# SENSOR_SCH_HDMI.net
KiCad netlist of a schematic drawn in EasyEDA
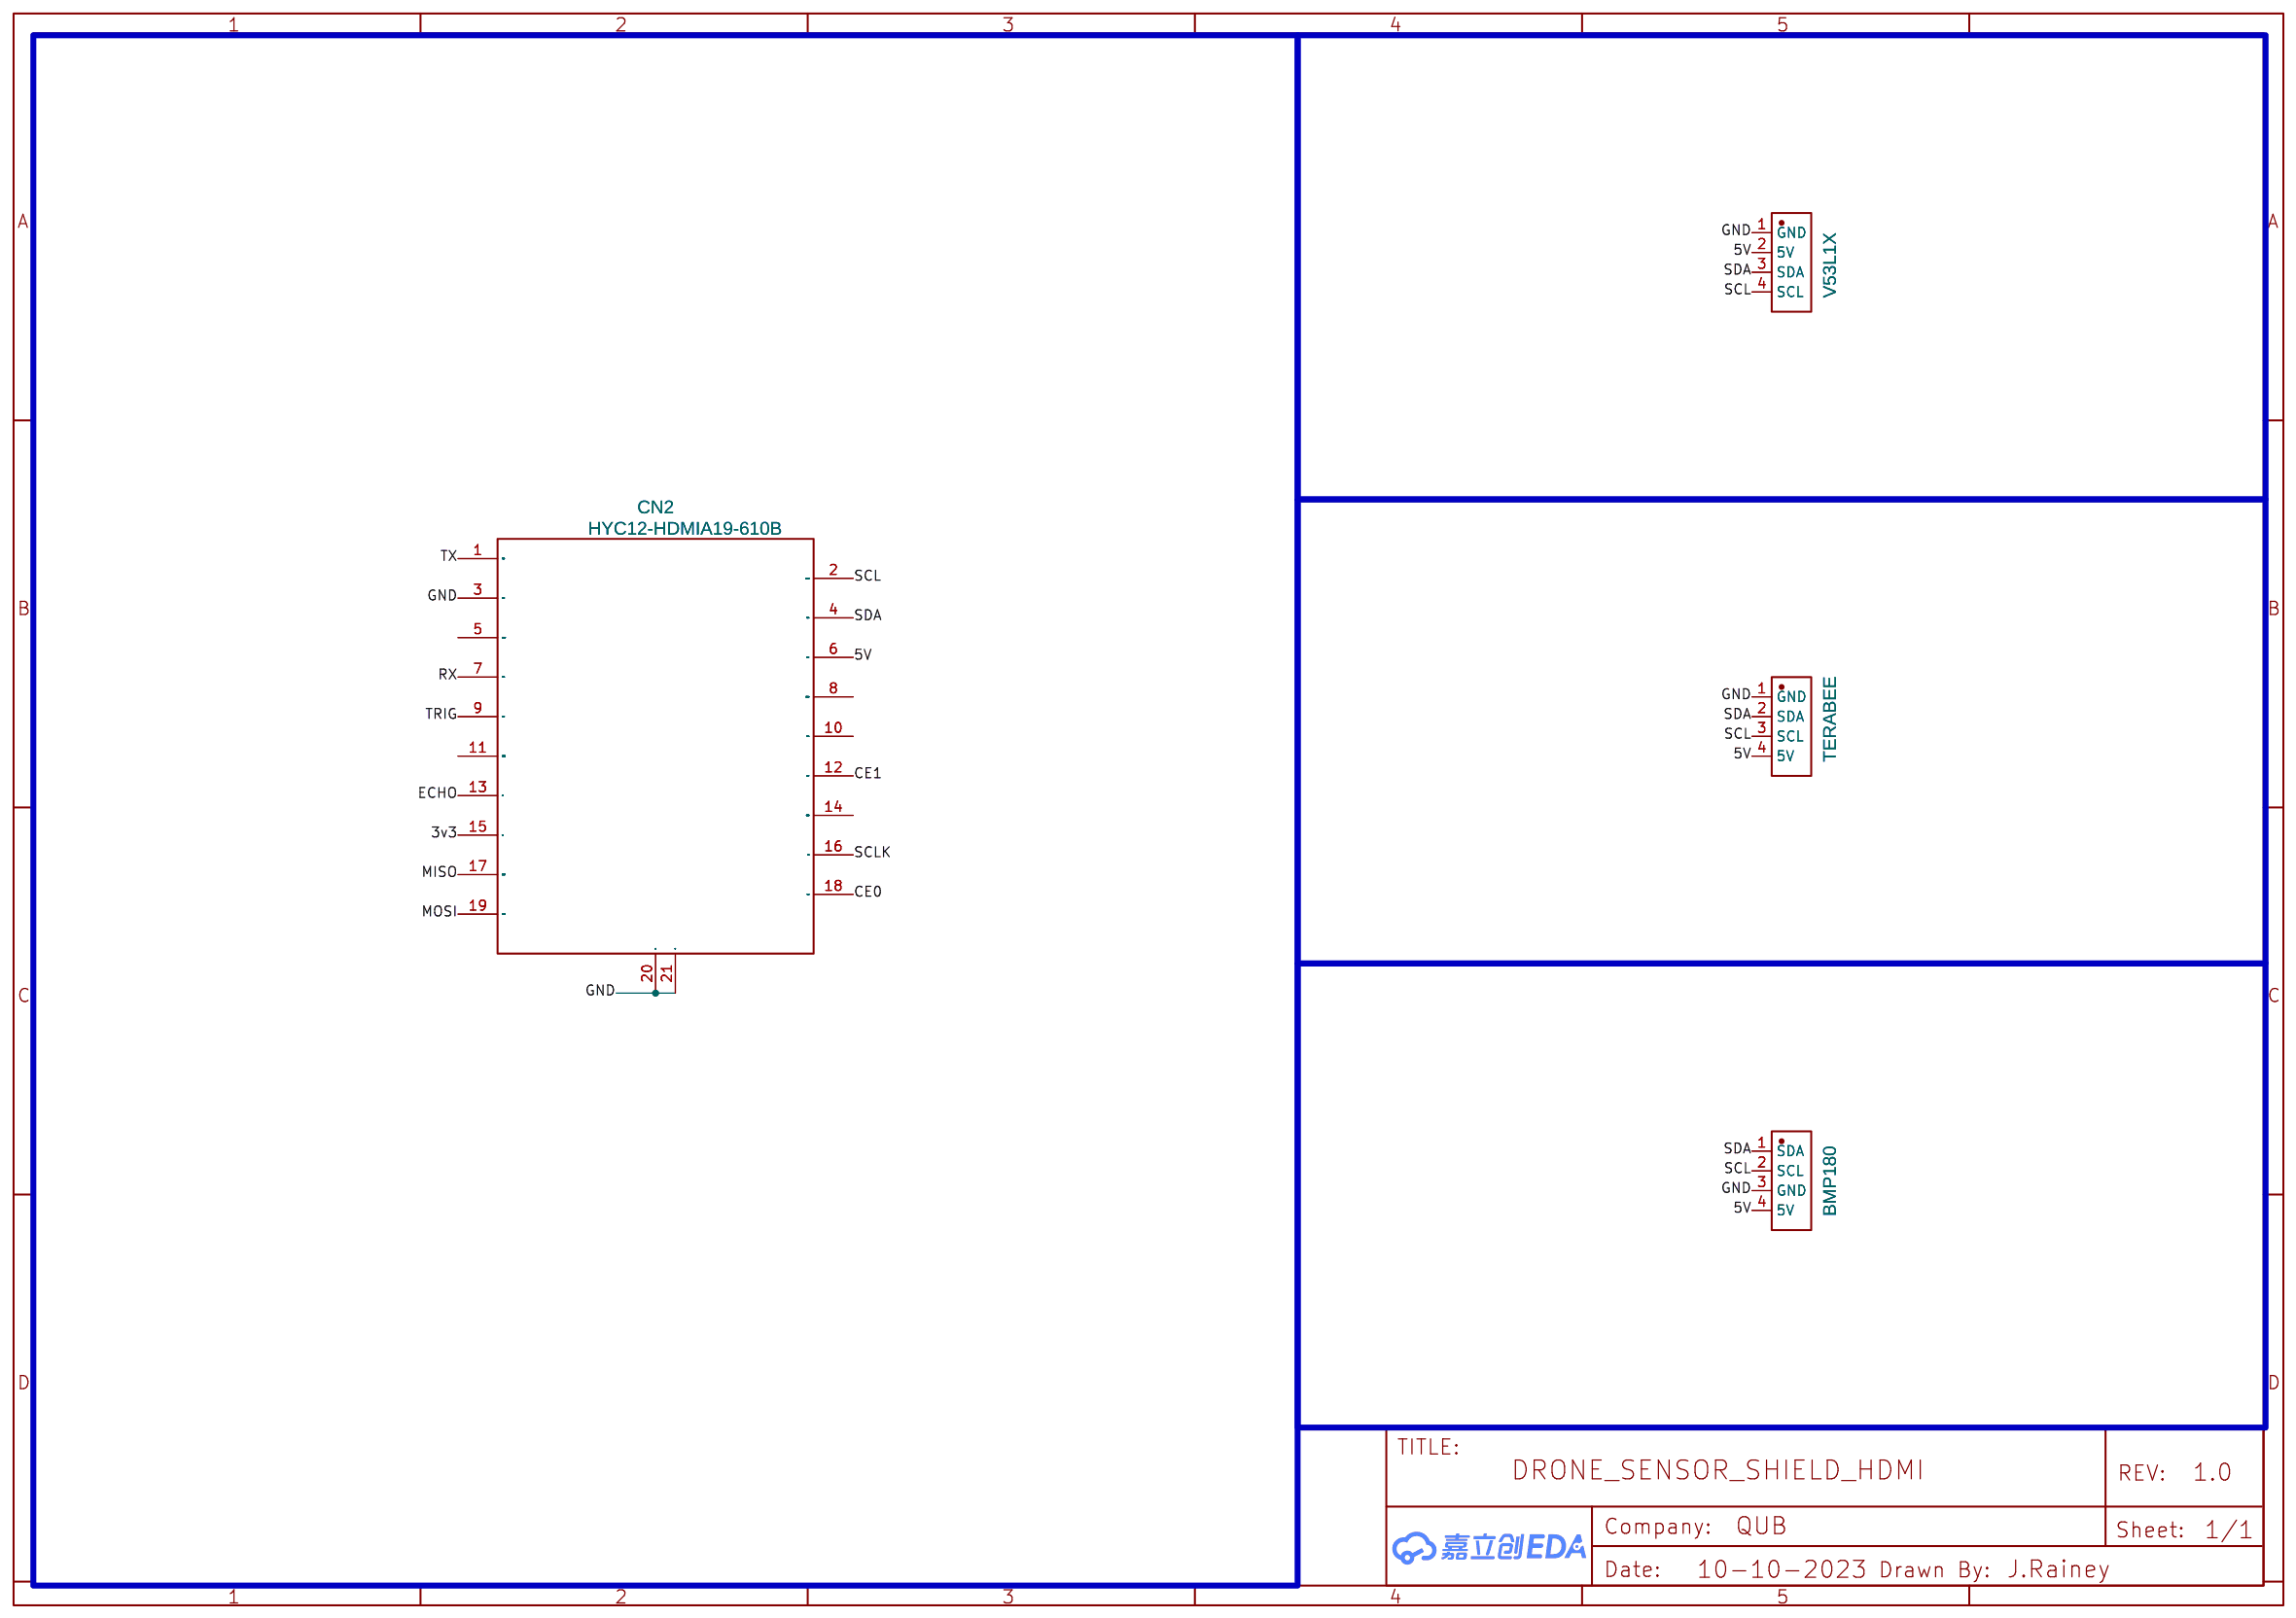
[diagram p0: schematic sheet]

(export (version "E")
  (design (tool "Eeschema 10.0.6"))
  (components
    (comp (ref "BMP180")
      (value "PZ254V-11-04P")
      (fields (field (name "BOM_Supplier Part") "C492403"))
      (libsource (lib "") (part "PZ254V-11-04P_2"))
    )
    (comp (ref "CN2")
      (value "HYC12-HDMIA19-610B")
      (fields (field (name "BOM_Supplier Part") "C711354"))
      (libsource (lib "") (part "HYC12-HDMIA19-610B"))
    )
    (comp (ref "TERABEE")
      (value "PZ254V-11-04P")
      (fields (field (name "BOM_Supplier Part") "C492403"))
      (libsource (lib "") (part "PZ254V-11-04P"))
    )
    (comp (ref "V53L1X")
      (value "PZ254V-11-04P")
      (fields (field (name "BOM_Supplier Part") "C492403"))
      (libsource (lib "") (part "PZ254V-11-04P_1"))
    )
  )
  (nets
    (net (code "1") (name "/3v3") (class "Default")
      (node (ref "CN2") (pin "15") (pinfunction "SCL_15") (pintype "unspecified"))
    )
    (net (code "2") (name "/5V") (class "Default")
      (node (ref "BMP180") (pin "4") (pinfunction "5V_4") (pintype "unspecified"))
      (node (ref "CN2") (pin "6") (pinfunction "TMDS_Data_1-_6") (pintype "unspecified"))
      (node (ref "TERABEE") (pin "4") (pinfunction "5V_4") (pintype "unspecified"))
      (node (ref "V53L1X") (pin "2") (pinfunction "5V_2") (pintype "unspecified"))
    )
    (net (code "3") (name "/CE0") (class "Default")
      (node (ref "CN2") (pin "18") (pinfunction "+5V_Power_18") (pintype "unspecified"))
    )
    (net (code "4") (name "/CE1") (class "Default")
      (node (ref "CN2") (pin "12") (pinfunction "TMDS_Clock-_12") (pintype "unspecified"))
    )
    (net (code "5") (name "/ECHO") (class "Default")
      (node (ref "CN2") (pin "13") (pinfunction "CEC_13") (pintype "unspecified"))
    )
    (net (code "6") (name "/GND") (class "Default")
      (node (ref "BMP180") (pin "3") (pinfunction "GND_3") (pintype "unspecified"))
      (node (ref "CN2") (pin "20") (pinfunction "EH_20") (pintype "unspecified"))
      (node (ref "CN2") (pin "21") (pinfunction "EH_21") (pintype "unspecified"))
      (node (ref "CN2") (pin "3") (pinfunction "TMDS_Data_2-_3") (pintype "unspecified"))
      (node (ref "TERABEE") (pin "1") (pinfunction "GND_1") (pintype "unspecified"))
      (node (ref "V53L1X") (pin "1") (pinfunction "GND_1") (pintype "unspecified"))
    )
    (net (code "7") (name "/MISO") (class "Default")
      (node (ref "CN2") (pin "17") (pinfunction "DDC/CEC_Ground_17") (pintype "unspecified"))
    )
    (net (code "8") (name "/MOSI") (class "Default")
      (node (ref "CN2") (pin "19") (pinfunction "Hot_Plug_Detect_19") (pintype "unspecified"))
    )
    (net (code "9") (name "/RX") (class "Default")
      (node (ref "CN2") (pin "7") (pinfunction "TMDS_Data_0+_7") (pintype "unspecified"))
    )
    (net (code "10") (name "/SCL") (class "Default")
      (node (ref "BMP180") (pin "2") (pinfunction "SCL_2") (pintype "unspecified"))
      (node (ref "CN2") (pin "2") (pinfunction "TMDS_Data_2_Shield_2") (pintype "unspecified"))
      (node (ref "TERABEE") (pin "3") (pinfunction "SCL_3") (pintype "unspecified"))
      (node (ref "V53L1X") (pin "4") (pinfunction "SCL_4") (pintype "unspecified"))
    )
    (net (code "11") (name "/SCLK") (class "Default")
      (node (ref "CN2") (pin "16") (pinfunction "SDA_16") (pintype "unspecified"))
    )
    (net (code "12") (name "/SDA") (class "Default")
      (node (ref "BMP180") (pin "1") (pinfunction "SDA_1") (pintype "unspecified"))
      (node (ref "CN2") (pin "4") (pinfunction "TMDS_Data_1+_4") (pintype "unspecified"))
      (node (ref "TERABEE") (pin "2") (pinfunction "SDA_2") (pintype "unspecified"))
      (node (ref "V53L1X") (pin "3") (pinfunction "SDA_3") (pintype "unspecified"))
    )
    (net (code "13") (name "/TRIG") (class "Default")
      (node (ref "CN2") (pin "9") (pinfunction "TMDS_Data_0-_9") (pintype "unspecified"))
    )
    (net (code "14") (name "/TX") (class "Default")
      (node (ref "CN2") (pin "1") (pinfunction "TMDS_Data_2+_1") (pintype "unspecified"))
    )
    (net (code "15") (name "unconnected-(CN2-Reserved_(N.C.)-Pad14)") (class "Default")
      (node (ref "CN2") (pin "14") (pinfunction "Reserved_(N.C.)_14") (pintype "unspecified"))
    )
    (net (code "16") (name "unconnected-(CN2-TMDS_Clock+-Pad10)") (class "Default")
      (node (ref "CN2") (pin "10") (pinfunction "TMDS_Clock+_10") (pintype "unspecified"))
    )
    (net (code "17") (name "unconnected-(CN2-TMDS_Clock_Shield-Pad11)") (class "Default")
      (node (ref "CN2") (pin "11") (pinfunction "TMDS_Clock_Shield_11") (pintype "unspecified"))
    )
    (net (code "18") (name "unconnected-(CN2-TMDS_Data_0_Shield-Pad8)") (class "Default")
      (node (ref "CN2") (pin "8") (pinfunction "TMDS_Data_0_Shield_8") (pintype "unspecified"))
    )
    (net (code "19") (name "unconnected-(CN2-TMDS_Data_1_Shield-Pad5)") (class "Default")
      (node (ref "CN2") (pin "5") (pinfunction "TMDS_Data_1_Shield_5") (pintype "unspecified"))
    )
  )
)
